# TemperatureSensor.net
KiCad netlist of a schematic drawn in Altium Designer
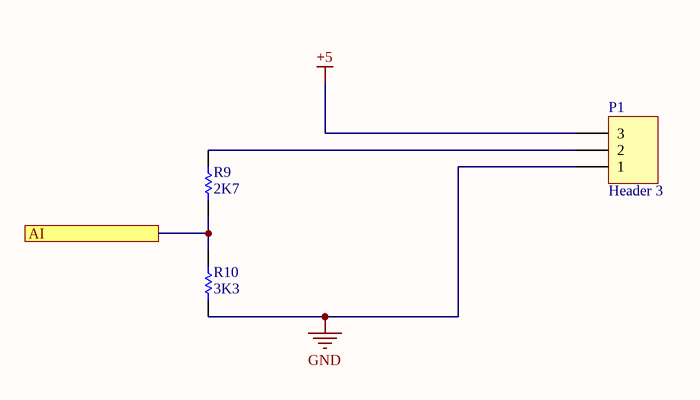
[diagram p0: TemperatureSensor.SchDoc]

(export (version "E")
  (design (tool "Eeschema 10.0.6"))
  (components
    (comp (ref "P1")
      (value "Header 3")
      (footprint "HDR1X3")
      (description "Header, 3-Pin")
      (fields (field (name "PUBLISHER") "Altium Limited"))
      (libsource (lib "Miscellaneous Connectors") (part "Header 3"))
    )
    (comp (ref "R9")
      (value "2K7")
      (footprint "RESC0603(1608)_N")
      (description "10K 0.1W 1% 0603 (1608 Metric)  SMD")
      (fields (field (name "POWER") "0.1 W") (field (name "TOLERANCE") "1 %"))
      (libsource (lib "Altium Content Vault") (part "RES"))
    )
    (comp (ref "R10")
      (value "3K3")
      (footprint "RESC0603(1608)_N")
      (description "10K 0.1W 1% 0603 (1608 Metric)  SMD")
      (fields (field (name "POWER") "0.1 W") (field (name "TOLERANCE") "1 %"))
      (libsource (lib "Altium Content Vault") (part "RES"))
    )
  )
  (nets
    (net (code "1") (name "+5") (class "Default")
      (node (ref "P1") (pin "3") (pinfunction "3_3") (pintype "passive"))
    )
    (net (code "2") (name "/AI") (class "Default")
      (node (ref "R10") (pin "2") (pinfunction "2_2") (pintype "passive"))
      (node (ref "R9") (pin "1") (pinfunction "1_1") (pintype "passive"))
    )
    (net (code "3") (name "GND") (class "Default")
      (node (ref "P1") (pin "1") (pinfunction "1_1") (pintype "passive"))
      (node (ref "R10") (pin "1") (pinfunction "1_1") (pintype "passive"))
    )
    (net (code "4") (name "Net-(P1-Pad2)") (class "Default")
      (node (ref "P1") (pin "2") (pinfunction "2_2") (pintype "passive"))
      (node (ref "R9") (pin "2") (pinfunction "2_2") (pintype "passive"))
    )
  )
)
